# Button_Board.net
KiCad netlist of a schematic drawn in EAGLE
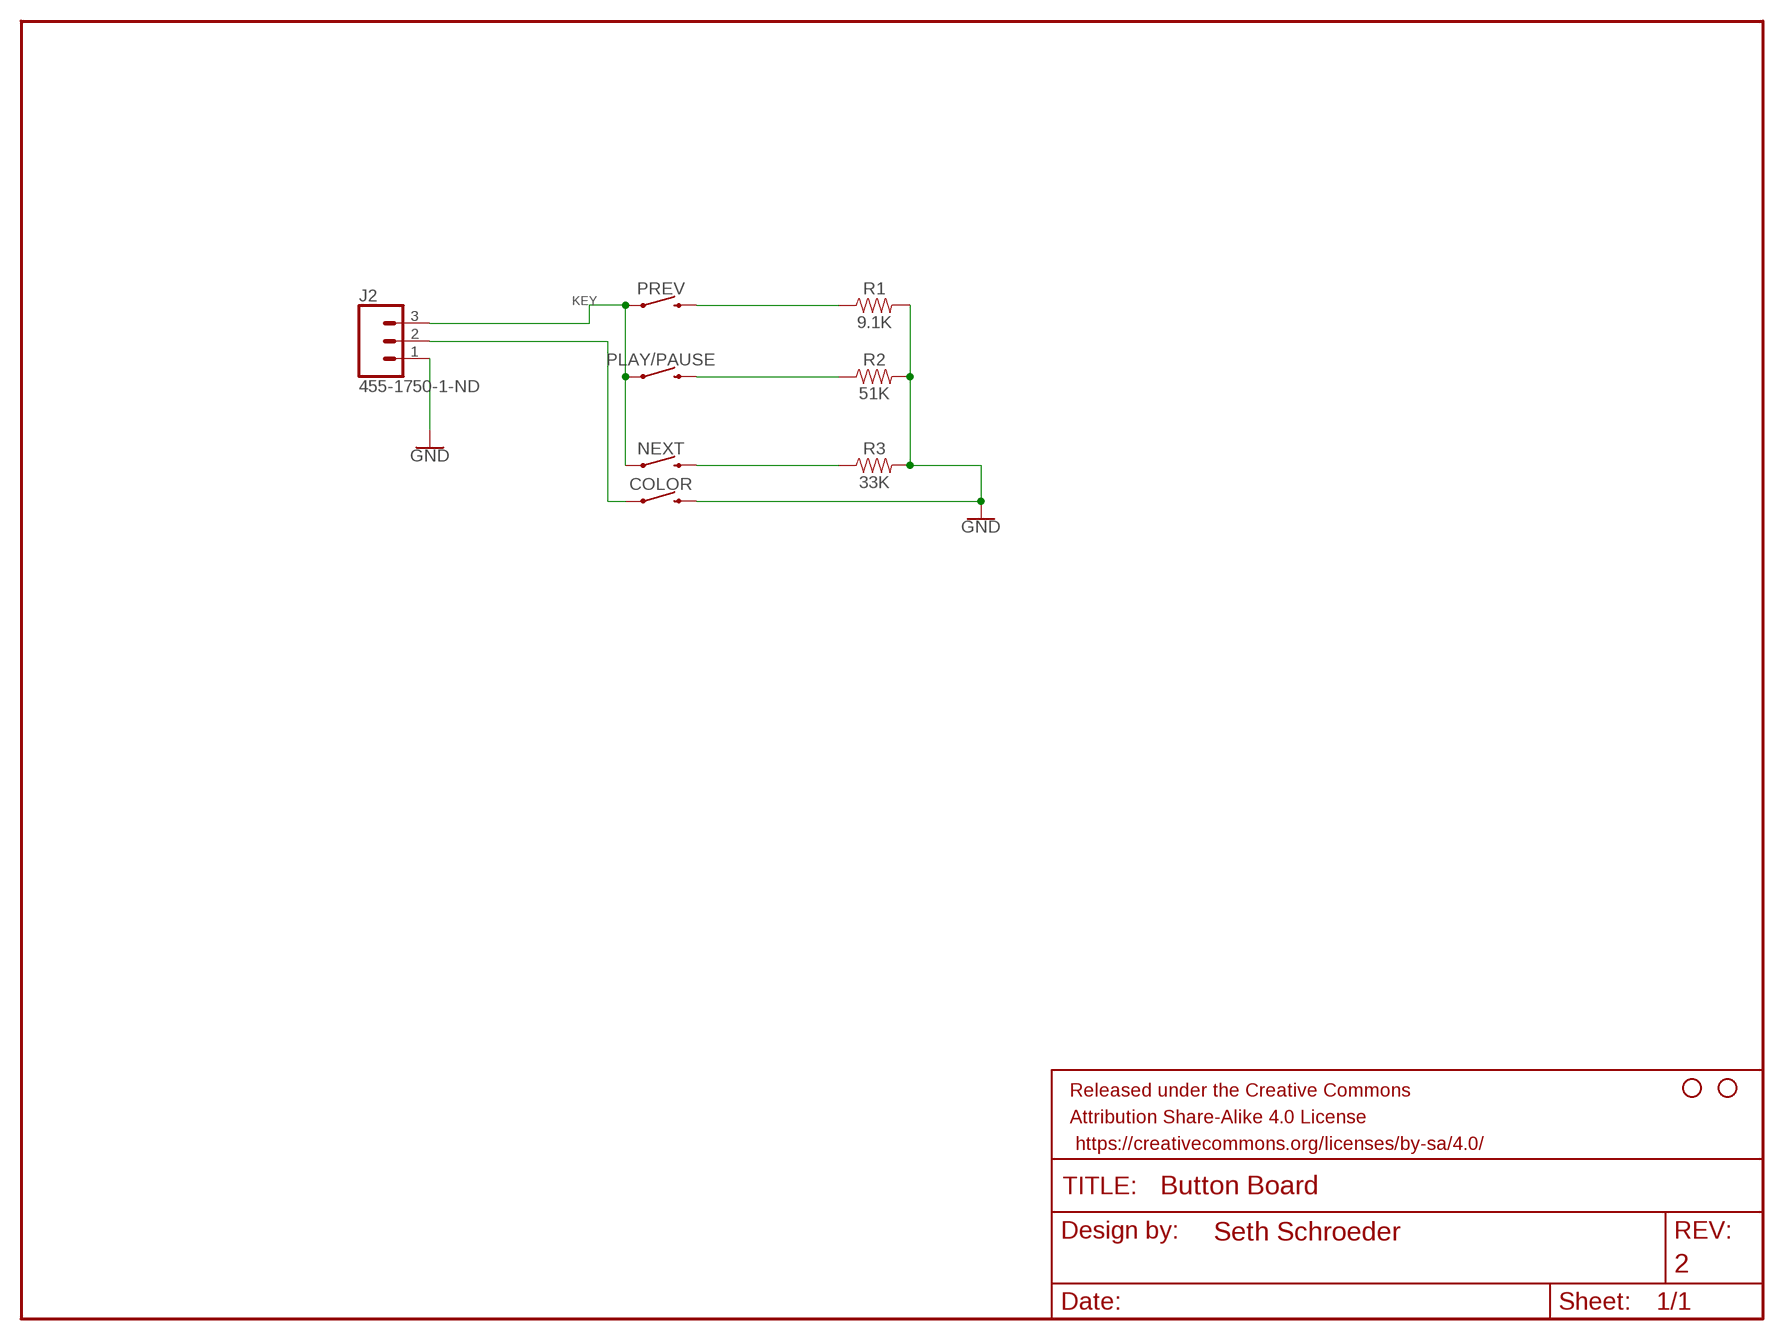
[diagram p0: schematic, sheet 1]

(export (version "E")
  (design (tool "Eeschema 10.0.6"))
  (components
    (comp (ref "COLOR")
      (value "MOMENTARY-SWITCH-SPST-PTH-12MM")
      (footprint "eagle-import:TACTILE_SWITCH_PTH_12MM")
      (libsource (lib "eagle-import") (part "MOMENTARY-SWITCH-SPST-PTH-12MM"))
    )
    (comp (ref "H1")
      (value "STAND-OFF")
      (footprint "eagle-import:STAND-OFF")
      (libsource (lib "eagle-import") (part "STAND-OFF"))
    )
    (comp (ref "H2")
      (value "STAND-OFF")
      (footprint "eagle-import:STAND-OFF")
      (libsource (lib "eagle-import") (part "STAND-OFF"))
    )
    (comp (ref "J2")
      (value "455-1750-1-ND")
      (footprint "eagle-import:1X03")
      (libsource (lib "eagle-import") (part "CONN_03"))
    )
    (comp (ref "ME")
      (value "Seth")
      (footprint "eagle-import:CREATIVE_COMMONS")
      (fields (field (name "DESIGNER") "Seth Schroeder") (field (name "REV") "2"))
      (libsource (lib "eagle-import") (part "FRAME-LETTER"))
    )
    (comp (ref "NEXT")
      (value "MOMENTARY-SWITCH-SPST-PTH-12MM")
      (footprint "eagle-import:TACTILE_SWITCH_PTH_12MM")
      (libsource (lib "eagle-import") (part "MOMENTARY-SWITCH-SPST-PTH-12MM"))
    )
    (comp (ref "PLAY/PAUSE")
      (value "MOMENTARY-SWITCH-SPST-PTH-12MM")
      (footprint "eagle-import:TACTILE_SWITCH_PTH_12MM")
      (libsource (lib "eagle-import") (part "MOMENTARY-SWITCH-SPST-PTH-12MM"))
    )
    (comp (ref "PREV")
      (value "MOMENTARY-SWITCH-SPST-PTH-12MM")
      (footprint "eagle-import:TACTILE_SWITCH_PTH_12MM")
      (libsource (lib "eagle-import") (part "MOMENTARY-SWITCH-SPST-PTH-12MM"))
    )
    (comp (ref "R1")
      (value "9.1K")
      (footprint "eagle-import:AXIAL-0.3")
      (libsource (lib "eagle-import") (part "RESISTORAXIAL-0.3"))
    )
    (comp (ref "R2")
      (value "51K")
      (footprint "eagle-import:AXIAL-0.3")
      (libsource (lib "eagle-import") (part "RESISTORAXIAL-0.3"))
    )
    (comp (ref "R3")
      (value "33K")
      (footprint "eagle-import:AXIAL-0.3")
      (libsource (lib "eagle-import") (part "RESISTORAXIAL-0.3"))
    )
  )
  (nets
    (net (code "1") (name "/KEY") (class "Default")
      (node (ref "J2") (pin "3") (pinfunction "3_3") (pintype "passive"))
      (node (ref "NEXT") (pin "1") (pinfunction "1_1") (pintype "passive"))
      (node (ref "PLAY/PAUSE") (pin "1") (pinfunction "1_1") (pintype "passive"))
      (node (ref "PREV") (pin "1") (pinfunction "1_1") (pintype "passive"))
    )
    (net (code "2") (name "GND") (class "Default")
      (node (ref "COLOR") (pin "3") (pinfunction "2_3") (pintype "passive"))
      (node (ref "J2") (pin "1") (pinfunction "1_1") (pintype "passive"))
      (node (ref "R1") (pin "P$2") (pinfunction "2_P$2") (pintype "passive"))
      (node (ref "R2") (pin "P$2") (pinfunction "2_P$2") (pintype "passive"))
      (node (ref "R3") (pin "P$2") (pinfunction "2_P$2") (pintype "passive"))
    )
    (net (code "3") (name "Net-(COLOR-Pad1)") (class "Default")
      (node (ref "COLOR") (pin "1") (pinfunction "1_1") (pintype "passive"))
      (node (ref "J2") (pin "2") (pinfunction "2_2") (pintype "passive"))
    )
    (net (code "4") (name "Net-(NEXT-2)") (class "Default")
      (node (ref "NEXT") (pin "3") (pinfunction "2_3") (pintype "passive"))
      (node (ref "R3") (pin "P$1") (pinfunction "1_P$1") (pintype "passive"))
    )
    (net (code "5") (name "Net-(PLAY/PAUSE-2)") (class "Default")
      (node (ref "PLAY/PAUSE") (pin "3") (pinfunction "2_3") (pintype "passive"))
      (node (ref "R2") (pin "P$1") (pinfunction "1_P$1") (pintype "passive"))
    )
    (net (code "6") (name "Net-(PREV-2)") (class "Default")
      (node (ref "PREV") (pin "3") (pinfunction "2_3") (pintype "passive"))
      (node (ref "R1") (pin "P$1") (pinfunction "1_P$1") (pintype "passive"))
    )
  )
)
